# PWRSUPPLY.net
KiCad netlist of a schematic drawn in Altium Designer
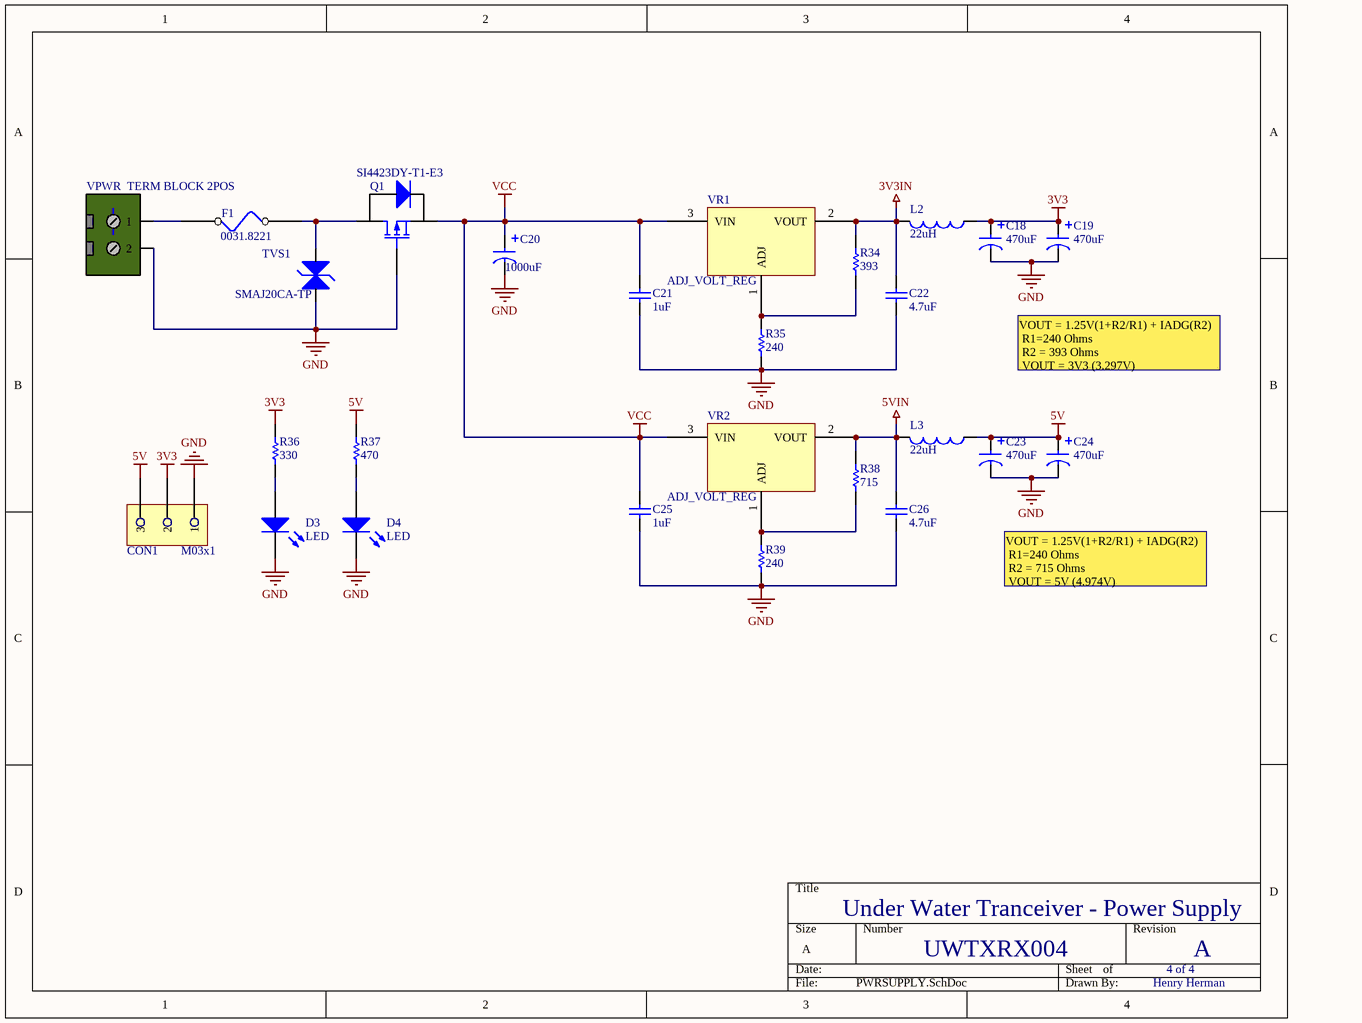
[diagram p0: PWRSUPPLY.SchDoc]

(export (version "E")
  (design (tool "Eeschema 10.0.6"))
  (components
    (comp (ref "C18")
      (value "470uF")
      (footprint "SM/CT_6032_12")
      (description "CAP")
      (fields (field (name "Comment") "CAP_POL"))
      (libsource (lib "Henry1_20_2010") (part "CAP_POL"))
    )
    (comp (ref "C19")
      (value "470uF")
      (footprint "SM/CT_6032_12")
      (description "CAP")
      (fields (field (name "Comment") "CAP_POL"))
      (libsource (lib "Henry1_20_2010") (part "CAP_POL"))
    )
    (comp (ref "C20")
      (value "1000uF")
      (footprint "CAP-CAN-SMD-POL-12.5mmDia")
      (description "CAP")
      (fields (field (name "Comment") "CAP_POL"))
      (libsource (lib "Henry1_20_2010") (part "CAP_POL"))
    )
    (comp (ref "C21")
      (value "1uF")
      (footprint "SM/C_0805")
      (description "CAP")
      (libsource (lib "Henry1_20_2010") (part "CAP"))
    )
    (comp (ref "C22")
      (value "4.7uF")
      (footprint "SM/C_0805")
      (description "CAP")
      (libsource (lib "Henry1_20_2010") (part "CAP"))
    )
    (comp (ref "C23")
      (value "470uF")
      (footprint "SM/CT_6032_12")
      (description "CAP")
      (fields (field (name "Comment") "CAP_POL"))
      (libsource (lib "Henry1_20_2010") (part "CAP_POL"))
    )
    (comp (ref "C24")
      (value "470uF")
      (footprint "SM/CT_6032_12")
      (description "CAP")
      (fields (field (name "Comment") "CAP_POL"))
      (libsource (lib "Henry1_20_2010") (part "CAP_POL"))
    )
    (comp (ref "C25")
      (value "1uF")
      (footprint "SM/C_0805")
      (description "CAP")
      (libsource (lib "Henry1_20_2010") (part "CAP"))
    )
    (comp (ref "C26")
      (value "4.7uF")
      (footprint "SM/C_0805")
      (description "CAP")
      (libsource (lib "Henry1_20_2010") (part "CAP"))
    )
    (comp (ref "CON1") (value "M03x1") (footprint "M03x1") (libsource (lib "Henry1_20_2010") (part "M03x1")))
    (comp (ref "D3") (value "LED") (footprint "LED-0805") (libsource (lib "Henry1_20_2010") (part "LED")))
    (comp (ref "D4") (value "LED") (footprint "LED-0805") (libsource (lib "Henry1_20_2010") (part "LED")))
    (comp (ref "F1")
      (value "0031.8221")
      (footprint "SCHURTER/SMD/2 PADS/0031.8221")
      (description "FUSEHOLDER BLACK FOR SMD 5X20MM")
      (libsource (lib "FriedParts") (part "FUSE"))
    )
    (comp (ref "L2")
      (value "22uH")
      (footprint "G_JMETRIC/TDK/SLE10145")
      (description "INDUCTOR SHIELD PWR 22UH 10145")
      (fields (field (name "MFRPARTNUM") "SLF10145T-220M1R9-PF"))
      (libsource (lib "FriedParts") (part "INDUCTOR"))
    )
    (comp (ref "L3")
      (value "22uH")
      (footprint "G_JMETRIC/TDK/SLE10145")
      (description "INDUCTOR SHIELD PWR 22UH 10145")
      (fields (field (name "MFRPARTNUM") "SLF10145T-220M1R9-PF"))
      (libsource (lib "FriedParts") (part "INDUCTOR"))
    )
    (comp (ref "Q1")
      (value "SI4423DY-T1-E3")
      (footprint "SOIC-8-Lead-Vishay-PFET")
      (description "mosfet,p ch,20v,10a,8soic; transistor polarity:p channel;")
      (libsource (lib "FriedParts") (part "P-Channel 20V D-S MOSFET"))
    )
    (comp (ref "R34")
      (value "393")
      (footprint "SM/R_0805")
      (description "Resistor")
      (fields (field (name "Comment") "Res") (field (name "PUBLISHER") "Altium Limited"))
      (libsource (lib "Henry1_20_2010") (part "Res"))
    )
    (comp (ref "R35")
      (value "240")
      (footprint "SM/R_0805")
      (description "Resistor")
      (fields (field (name "Comment") "Res") (field (name "PUBLISHER") "Altium Limited"))
      (libsource (lib "Henry1_20_2010") (part "Res"))
    )
    (comp (ref "R36")
      (value "330")
      (footprint "SM/R_0805")
      (description "Resistor")
      (fields (field (name "Comment") "Res") (field (name "PUBLISHER") "Altium Limited"))
      (libsource (lib "Henry1_20_2010") (part "Res"))
    )
    (comp (ref "R37")
      (value "470")
      (footprint "SM/R_0805")
      (description "Resistor")
      (fields (field (name "Comment") "Res") (field (name "PUBLISHER") "Altium Limited"))
      (libsource (lib "Henry1_20_2010") (part "Res"))
    )
    (comp (ref "R38")
      (value "715")
      (footprint "SM/R_0805")
      (description "Resistor")
      (fields (field (name "Comment") "Res") (field (name "PUBLISHER") "Altium Limited"))
      (libsource (lib "Henry1_20_2010") (part "Res"))
    )
    (comp (ref "R39")
      (value "240")
      (footprint "SM/R_0805")
      (description "Resistor")
      (fields (field (name "Comment") "Res") (field (name "PUBLISHER") "Altium Limited"))
      (libsource (lib "Henry1_20_2010") (part "Res"))
    )
    (comp (ref "TVS1")
      (value "SMAJ20CA-TP")
      (footprint "D0-214AC")
      (description "TVS 400W 12V BIDIRECT SMA")
      (fields (field (name "MFRPARTNUM") "SMAJ12CA-TP"))
      (libsource (lib "FriedParts") (part "SMAJ12CA-TPMC"))
    )
    (comp (ref "VPWR")
      (value "TERM BLOCK 2POS")
      (footprint "Conn-ScrewTerminal-2pin-Phoenix")
      (libsource (lib "Henry1_20_2010") (part "2Pin-PhoenixTerminalBlock"))
    )
    (comp (ref "VR1")
      (value "ADJ_VOLT_REG")
      (footprint "LM317-SOT233-POS-ADJ-VOLT_REG")
      (libsource (lib "Henry1_20_2010") (part "ADJ_VOLT_REG"))
    )
    (comp (ref "VR2")
      (value "ADJ_VOLT_REG")
      (footprint "LM317-SOT233-POS-ADJ-VOLT_REG")
      (libsource (lib "Henry1_20_2010") (part "ADJ_VOLT_REG"))
    )
  )
  (nets
    (net (code "1") (name "3V3") (class "Default")
      (node (ref "C18") (pin "1") (pinfunction "1_1") (pintype "passive"))
      (node (ref "C19") (pin "1") (pinfunction "1_1") (pintype "passive"))
      (node (ref "CON1") (pin "2") (pinfunction "2_2") (pintype "passive"))
      (node (ref "L2") (pin "1") (pinfunction "1_1") (pintype "passive"))
      (node (ref "R36") (pin "1") (pinfunction "1_1") (pintype "passive"))
    )
    (net (code "2") (name "3V3IN") (class "Default")
      (node (ref "C22") (pin "2") (pinfunction "2_2") (pintype "passive"))
      (node (ref "L2") (pin "2") (pinfunction "2_2") (pintype "passive"))
      (node (ref "R34") (pin "2") (pinfunction "2_2") (pintype "passive"))
      (node (ref "VR1") (pin "2") (pinfunction "VOUT_2") (pintype "passive"))
    )
    (net (code "3") (name "5V") (class "Default")
      (node (ref "C23") (pin "1") (pinfunction "1_1") (pintype "passive"))
      (node (ref "C24") (pin "1") (pinfunction "1_1") (pintype "passive"))
      (node (ref "CON1") (pin "3") (pinfunction "3_3") (pintype "passive"))
      (node (ref "L3") (pin "1") (pinfunction "1_1") (pintype "passive"))
      (node (ref "R37") (pin "1") (pinfunction "1_1") (pintype "passive"))
    )
    (net (code "4") (name "5VIN") (class "Default")
      (node (ref "C26") (pin "2") (pinfunction "2_2") (pintype "passive"))
      (node (ref "L3") (pin "2") (pinfunction "2_2") (pintype "passive"))
      (node (ref "R38") (pin "1") (pinfunction "1_1") (pintype "passive"))
      (node (ref "VR2") (pin "2") (pinfunction "VOUT_2") (pintype "passive"))
    )
    (net (code "5") (name "GND") (class "Default")
      (node (ref "C18") (pin "2") (pinfunction "2_2") (pintype "passive"))
      (node (ref "C19") (pin "2") (pinfunction "2_2") (pintype "passive"))
      (node (ref "C20") (pin "2") (pinfunction "2_2") (pintype "passive"))
      (node (ref "C21") (pin "1") (pinfunction "1_1") (pintype "passive"))
      (node (ref "C22") (pin "1") (pinfunction "1_1") (pintype "passive"))
      (node (ref "C23") (pin "2") (pinfunction "2_2") (pintype "passive"))
      (node (ref "C24") (pin "2") (pinfunction "2_2") (pintype "passive"))
      (node (ref "C25") (pin "1") (pinfunction "1_1") (pintype "passive"))
      (node (ref "C26") (pin "1") (pinfunction "1_1") (pintype "passive"))
      (node (ref "CON1") (pin "1") (pinfunction "1_1") (pintype "passive"))
      (node (ref "D3") (pin "2") (pinfunction "K_2") (pintype "passive"))
      (node (ref "D4") (pin "2") (pinfunction "K_2") (pintype "passive"))
      (node (ref "Q1") (pin "G") (pinfunction "G_G") (pintype "passive"))
      (node (ref "R35") (pin "1") (pinfunction "1_1") (pintype "passive"))
      (node (ref "R39") (pin "1") (pinfunction "1_1") (pintype "passive"))
      (node (ref "TVS1") (pin "C") (pinfunction "1_C") (pintype "passive"))
      (node (ref "VPWR") (pin "2") (pinfunction "2_2") (pintype "passive"))
    )
    (net (code "6") (name "Net-(D3-A)") (class "Default")
      (node (ref "D3") (pin "1") (pinfunction "A_1") (pintype "passive"))
      (node (ref "R36") (pin "2") (pinfunction "2_2") (pintype "passive"))
    )
    (net (code "7") (name "Net-(D4-A)") (class "Default")
      (node (ref "D4") (pin "1") (pinfunction "A_1") (pintype "passive"))
      (node (ref "R37") (pin "2") (pinfunction "2_2") (pintype "passive"))
    )
    (net (code "8") (name "Net-(F1-Pad1)") (class "Default")
      (node (ref "F1") (pin "1") (pinfunction "1_1") (pintype "passive"))
      (node (ref "VPWR") (pin "1") (pinfunction "1_1") (pintype "passive"))
    )
    (net (code "9") (name "Net-(TVS1-2)") (class "Default")
      (node (ref "F1") (pin "2") (pinfunction "2_2") (pintype "passive"))
      (node (ref "Q1") (pin "D") (pinfunction "D_D") (pintype "passive"))
      (node (ref "TVS1") (pin "A") (pinfunction "2_A") (pintype "passive"))
    )
    (net (code "10") (name "Net-(VR1-ADJ)") (class "Default")
      (node (ref "R34") (pin "1") (pinfunction "1_1") (pintype "passive"))
      (node (ref "R35") (pin "2") (pinfunction "2_2") (pintype "passive"))
      (node (ref "VR1") (pin "1") (pinfunction "ADJ_1") (pintype "passive"))
    )
    (net (code "11") (name "Net-(VR2-ADJ)") (class "Default")
      (node (ref "R38") (pin "2") (pinfunction "2_2") (pintype "passive"))
      (node (ref "R39") (pin "2") (pinfunction "2_2") (pintype "passive"))
      (node (ref "VR2") (pin "1") (pinfunction "ADJ_1") (pintype "passive"))
    )
    (net (code "12") (name "VCC") (class "Default")
      (node (ref "C20") (pin "1") (pinfunction "1_1") (pintype "passive"))
      (node (ref "C21") (pin "2") (pinfunction "2_2") (pintype "passive"))
      (node (ref "C25") (pin "2") (pinfunction "2_2") (pintype "passive"))
      (node (ref "Q1") (pin "S") (pinfunction "S_S") (pintype "passive"))
      (node (ref "VR1") (pin "3") (pinfunction "VIN_3") (pintype "passive"))
      (node (ref "VR2") (pin "3") (pinfunction "VIN_3") (pintype "passive"))
    )
  )
)
